# Phiips_212_r2.net
KiCad netlist of a schematic drawn in EAGLE
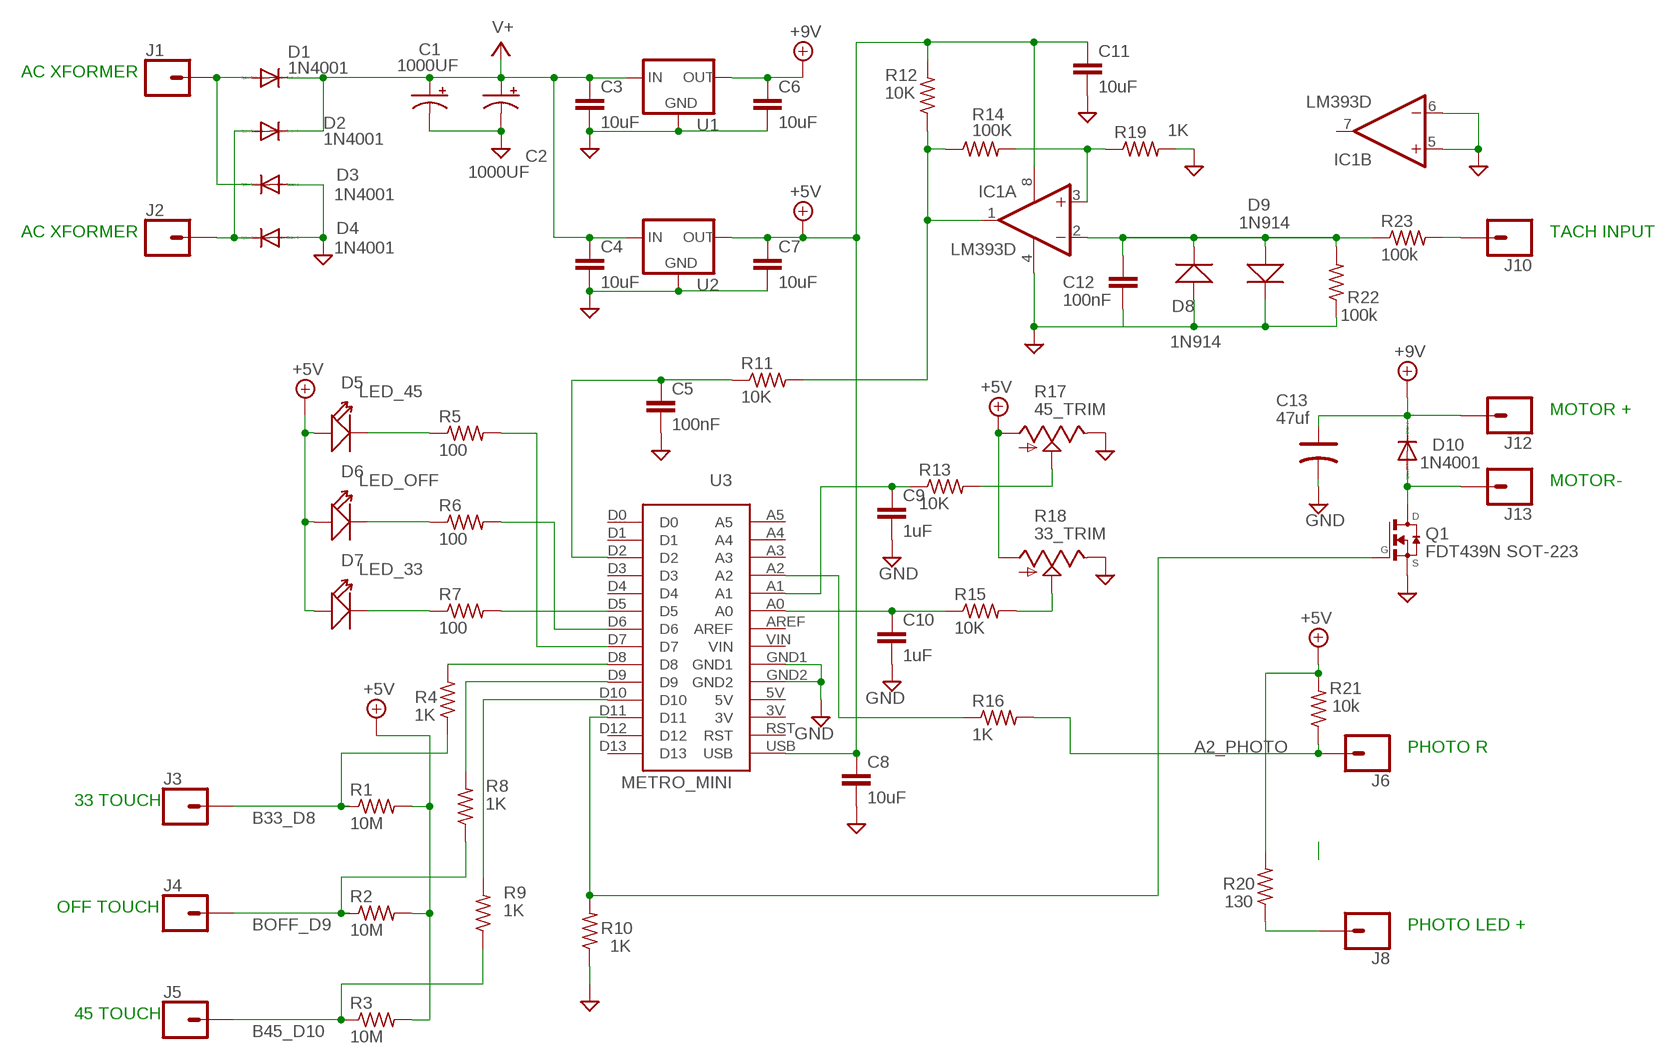
[diagram p0: schematic, sheet 1]

(export (version "E")
  (design (tool "Eeschema 10.0.6"))
  (components
    (comp (ref "C1")
      (value "1000UF")
      (footprint "eagle-import:CAPPAD1700W60L1040D500P")
      (libsource (lib "eagle-import") (part "1000UF"))
    )
    (comp (ref "C2")
      (value "1000UF")
      (footprint "eagle-import:CAPPAD1700W60L1040D500P")
      (libsource (lib "eagle-import") (part "1000UF"))
    )
    (comp (ref "C3")
      (value "10uF")
      (footprint "eagle-import:1206")
      (libsource (lib "eagle-import") (part "10UF-1206-6.3V-20%"))
    )
    (comp (ref "C4")
      (value "10uF")
      (footprint "eagle-import:1206")
      (libsource (lib "eagle-import") (part "10UF-1206-6.3V-20%"))
    )
    (comp (ref "C5")
      (value "100nF")
      (footprint "eagle-import:0805")
      (libsource (lib "eagle-import") (part "10UF-0805-10V-10%"))
    )
    (comp (ref "C6")
      (value "10uF")
      (footprint "eagle-import:1206")
      (libsource (lib "eagle-import") (part "10UF-1206-6.3V-20%"))
    )
    (comp (ref "C7")
      (value "10uF")
      (footprint "eagle-import:1206")
      (libsource (lib "eagle-import") (part "10UF-1206-6.3V-20%"))
    )
    (comp (ref "C8")
      (value "10uF")
      (footprint "eagle-import:1206")
      (libsource (lib "eagle-import") (part "10UF-1206-6.3V-20%"))
    )
    (comp (ref "C9")
      (value "1uF")
      (footprint "eagle-import:1206")
      (libsource (lib "eagle-import") (part "10UF-1206-6.3V-20%"))
    )
    (comp (ref "C10")
      (value "1uF")
      (footprint "eagle-import:1206")
      (libsource (lib "eagle-import") (part "10UF-1206-6.3V-20%"))
    )
    (comp (ref "C11")
      (value "10uF")
      (footprint "eagle-import:1206")
      (libsource (lib "eagle-import") (part "10UF-1206-6.3V-20%"))
    )
    (comp (ref "C12")
      (value "100nF")
      (footprint "eagle-import:0805")
      (libsource (lib "eagle-import") (part "10UF-0805-10V-10%"))
    )
    (comp (ref "C13")
      (value "47uf")
      (footprint "eagle-import:AVX-D")
      (fields (field (name "MPN") "TAJD477*006#NJ"))
      (libsource (lib "eagle-import") (part "TANTALUM-SMD-470UF-6.3V(AVX-D)"))
    )
    (comp (ref "D1")
      (value "1N4001")
      (footprint "eagle-import:DO41-10")
      (libsource (lib "eagle-import") (part "1N4004"))
    )
    (comp (ref "D2")
      (value "1N4001")
      (footprint "eagle-import:DO41-10")
      (libsource (lib "eagle-import") (part "1N4004"))
    )
    (comp (ref "D3")
      (value "1N4001")
      (footprint "eagle-import:DO41-10")
      (libsource (lib "eagle-import") (part "1N4004"))
    )
    (comp (ref "D4")
      (value "1N4001")
      (footprint "eagle-import:DO41-10")
      (libsource (lib "eagle-import") (part "1N4004"))
    )
    (comp (ref "D5")
      (value "LED_45")
      (footprint "eagle-import:LED2-2.54-D5.0MM")
      (fields (field (name "MPN") "504WC"))
      (libsource (lib "eagle-import") (part "DIP-LED-TRANSPARENT-WHITE(2P-D5MM)"))
    )
    (comp (ref "D6")
      (value "LED_OFF")
      (footprint "eagle-import:LED2-2.54-D5.0MM")
      (fields (field (name "MPN") "504WC"))
      (libsource (lib "eagle-import") (part "DIP-LED-TRANSPARENT-WHITE(2P-D5MM)"))
    )
    (comp (ref "D7")
      (value "LED_33")
      (footprint "eagle-import:LED2-2.54-D5.0MM")
      (fields (field (name "MPN") "504WC"))
      (libsource (lib "eagle-import") (part "DIP-LED-TRANSPARENT-WHITE(2P-D5MM)"))
    )
    (comp (ref "D8")
      (value "1N914")
      (footprint "eagle-import:DO-41")
      (fields (field (name "MPN") "1N4004"))
      (libsource (lib "eagle-import") (part "DIP-DIODE-400V-1A(DO-41)"))
    )
    (comp (ref "D9")
      (value "1N914")
      (footprint "eagle-import:DO-41")
      (fields (field (name "MPN") "1N4004"))
      (libsource (lib "eagle-import") (part "DIP-DIODE-400V-1A(DO-41)"))
    )
    (comp (ref "D10")
      (value "1N4001")
      (footprint "eagle-import:DO41-10")
      (libsource (lib "eagle-import") (part "1N4004"))
    )
    (comp (ref "IC1")
      (value "LM393D")
      (footprint "eagle-import:SO08")
      (libsource (lib "eagle-import") (part "LM393D"))
    )
    (comp (ref "J1")
      (value "CONN_01OFFSET")
      (footprint "eagle-import:1X01_OFFSET")
      (libsource (lib "eagle-import") (part "CONN_01OFFSET"))
    )
    (comp (ref "J2")
      (value "CONN_01OFFSET")
      (footprint "eagle-import:1X01_OFFSET")
      (libsource (lib "eagle-import") (part "CONN_01OFFSET"))
    )
    (comp (ref "J3")
      (value "CONN_01OFFSET")
      (footprint "eagle-import:1X01_OFFSET")
      (libsource (lib "eagle-import") (part "CONN_01OFFSET"))
    )
    (comp (ref "J4")
      (value "CONN_01OFFSET")
      (footprint "eagle-import:1X01_OFFSET")
      (libsource (lib "eagle-import") (part "CONN_01OFFSET"))
    )
    (comp (ref "J5")
      (value "CONN_01OFFSET")
      (footprint "eagle-import:1X01_OFFSET")
      (libsource (lib "eagle-import") (part "CONN_01OFFSET"))
    )
    (comp (ref "J6")
      (value "CONN_01OFFSET")
      (footprint "eagle-import:1X01_OFFSET")
      (libsource (lib "eagle-import") (part "CONN_01OFFSET"))
    )
    (comp (ref "J8")
      (value "CONN_01OFFSET")
      (footprint "eagle-import:1X01_OFFSET")
      (libsource (lib "eagle-import") (part "CONN_01OFFSET"))
    )
    (comp (ref "J10")
      (value "CONN_01OFFSET")
      (footprint "eagle-import:1X01_OFFSET")
      (libsource (lib "eagle-import") (part "CONN_01OFFSET"))
    )
    (comp (ref "J12")
      (value "CONN_01OFFSET")
      (footprint "eagle-import:1X01_OFFSET")
      (libsource (lib "eagle-import") (part "CONN_01OFFSET"))
    )
    (comp (ref "J13")
      (value "CONN_01OFFSET")
      (footprint "eagle-import:1X01_OFFSET")
      (libsource (lib "eagle-import") (part "CONN_01OFFSET"))
    )
    (comp (ref "Q1")
      (value "FDT439N SOT-223")
      (footprint "eagle-import:SOT-223")
      (libsource (lib "eagle-import") (part "FDT439NSOT-223"))
    )
    (comp (ref "R1")
      (value "10M")
      (footprint "eagle-import:M1206")
      (libsource (lib "eagle-import") (part "R-US_M1206"))
    )
    (comp (ref "R2")
      (value "10M")
      (footprint "eagle-import:M1206")
      (libsource (lib "eagle-import") (part "R-US_M1206"))
    )
    (comp (ref "R3")
      (value "10M")
      (footprint "eagle-import:M1206")
      (libsource (lib "eagle-import") (part "R-US_M1206"))
    )
    (comp (ref "R4")
      (value "1K")
      (footprint "eagle-import:M1206")
      (libsource (lib "eagle-import") (part "R-US_M1206"))
    )
    (comp (ref "R5")
      (value "100")
      (footprint "eagle-import:M1206")
      (libsource (lib "eagle-import") (part "R-US_M1206"))
    )
    (comp (ref "R6")
      (value "100")
      (footprint "eagle-import:M1206")
      (libsource (lib "eagle-import") (part "R-US_M1206"))
    )
    (comp (ref "R7")
      (value "100")
      (footprint "eagle-import:M1206")
      (libsource (lib "eagle-import") (part "R-US_M1206"))
    )
    (comp (ref "R8")
      (value "1K")
      (footprint "eagle-import:M1206")
      (libsource (lib "eagle-import") (part "R-US_M1206"))
    )
    (comp (ref "R9")
      (value "1K")
      (footprint "eagle-import:M1206")
      (libsource (lib "eagle-import") (part "R-US_M1206"))
    )
    (comp (ref "R10")
      (value "1K")
      (footprint "eagle-import:M1206")
      (libsource (lib "eagle-import") (part "R-US_M1206"))
    )
    (comp (ref "R11")
      (value "10K")
      (footprint "eagle-import:M1206")
      (libsource (lib "eagle-import") (part "R-US_M1206"))
    )
    (comp (ref "R12")
      (value "10K")
      (footprint "eagle-import:M1206")
      (libsource (lib "eagle-import") (part "R-US_M1206"))
    )
    (comp (ref "R13")
      (value "10K")
      (footprint "eagle-import:M1206")
      (libsource (lib "eagle-import") (part "R-US_M1206"))
    )
    (comp (ref "R14")
      (value "100K")
      (footprint "eagle-import:M1206")
      (libsource (lib "eagle-import") (part "R-US_M1206"))
    )
    (comp (ref "R15")
      (value "10K")
      (footprint "eagle-import:M1206")
      (libsource (lib "eagle-import") (part "R-US_M1206"))
    )
    (comp (ref "R16")
      (value "1K")
      (footprint "eagle-import:M1206")
      (libsource (lib "eagle-import") (part "R-US_M1206"))
    )
    (comp (ref "R17")
      (value "45_TRIM")
      (footprint "eagle-import:PH212_POT")
      (libsource (lib "eagle-import") (part "POTS212_POT"))
    )
    (comp (ref "R18")
      (value "33_TRIM")
      (footprint "eagle-import:PH212_POT")
      (libsource (lib "eagle-import") (part "POTS212_POT"))
    )
    (comp (ref "R19")
      (value "1K")
      (footprint "eagle-import:M1206")
      (libsource (lib "eagle-import") (part "R-US_M1206"))
    )
    (comp (ref "R20")
      (value "130")
      (footprint "eagle-import:M1206")
      (libsource (lib "eagle-import") (part "R-US_M1206"))
    )
    (comp (ref "R21")
      (value "10k")
      (footprint "eagle-import:M1206")
      (libsource (lib "eagle-import") (part "R-US_M1206"))
    )
    (comp (ref "R22")
      (value "100k")
      (footprint "eagle-import:M1206")
      (libsource (lib "eagle-import") (part "R-US_M1206"))
    )
    (comp (ref "R23")
      (value "100k")
      (footprint "eagle-import:M1206")
      (libsource (lib "eagle-import") (part "R-US_M1206"))
    )
    (comp (ref "U1")
      (value "V_REG_78XXSIDE")
      (footprint "eagle-import:78XXL")
      (libsource (lib "eagle-import") (part "V_REG_78XXSIDE"))
    )
    (comp (ref "U2")
      (value "V_REG_78XXSIDE")
      (footprint "eagle-import:78XXL")
      (libsource (lib "eagle-import") (part "V_REG_78XXSIDE"))
    )
    (comp (ref "U3")
      (value "METRO_MINI")
      (footprint "eagle-import:METRO_MINI")
      (libsource (lib "eagle-import") (part "METRO_MINI"))
    )
  )
  (nets
    (net (code "1") (name "+5V") (class "Default")
      (node (ref "C11") (pin "1") (pinfunction "1_1") (pintype "passive"))
      (node (ref "C7") (pin "1") (pinfunction "1_1") (pintype "passive"))
      (node (ref "C8") (pin "1") (pinfunction "1_1") (pintype "passive"))
      (node (ref "D5") (pin "+") (pinfunction "+_+") (pintype "passive"))
      (node (ref "D6") (pin "+") (pinfunction "+_+") (pintype "passive"))
      (node (ref "D7") (pin "+") (pinfunction "+_+") (pintype "passive"))
      (node (ref "IC1") (pin "8") (pinfunction "V+_8") (pintype "power_in"))
      (node (ref "R1") (pin "2") (pinfunction "2_2") (pintype "passive"))
      (node (ref "R12") (pin "2") (pinfunction "2_2") (pintype "passive"))
      (node (ref "R17") (pin "1") (pinfunction "A_1") (pintype "passive"))
      (node (ref "R18") (pin "1") (pinfunction "A_1") (pintype "passive"))
      (node (ref "R2") (pin "2") (pinfunction "2_2") (pintype "passive"))
      (node (ref "R20") (pin "2") (pinfunction "2_2") (pintype "passive"))
      (node (ref "R21") (pin "2") (pinfunction "2_2") (pintype "passive"))
      (node (ref "R3") (pin "2") (pinfunction "2_2") (pintype "passive"))
      (node (ref "U2") (pin "OUT") (pinfunction "OUT_OUT") (pintype "passive"))
      (node (ref "U3") (pin "USB") (pinfunction "USB_USB") (pintype "power_in"))
    )
    (net (code "2") (name "+9V") (class "Default")
      (node (ref "C13") (pin "+") (pinfunction "+_+") (pintype "passive"))
      (node (ref "C6") (pin "1") (pinfunction "1_1") (pintype "passive"))
      (node (ref "D10") (pin "C") (pinfunction "C_C") (pintype "passive"))
      (node (ref "J12") (pin "1") (pinfunction "1_1") (pintype "passive"))
      (node (ref "U1") (pin "OUT") (pinfunction "OUT_OUT") (pintype "passive"))
    )
    (net (code "3") (name "/A2_PHOTO") (class "Default")
      (node (ref "J6") (pin "1") (pinfunction "1_1") (pintype "passive"))
      (node (ref "R16") (pin "2") (pinfunction "2_2") (pintype "passive"))
      (node (ref "R21") (pin "1") (pinfunction "1_1") (pintype "passive"))
    )
    (net (code "4") (name "/B33_D8") (class "Default")
      (node (ref "J3") (pin "1") (pinfunction "1_1") (pintype "passive"))
      (node (ref "R1") (pin "1") (pinfunction "1_1") (pintype "passive"))
      (node (ref "R4") (pin "1") (pinfunction "1_1") (pintype "passive"))
    )
    (net (code "5") (name "/B45_D10") (class "Default")
      (node (ref "J5") (pin "1") (pinfunction "1_1") (pintype "passive"))
      (node (ref "R3") (pin "1") (pinfunction "1_1") (pintype "passive"))
      (node (ref "R9") (pin "1") (pinfunction "1_1") (pintype "passive"))
    )
    (net (code "6") (name "/BOFF_D9") (class "Default")
      (node (ref "J4") (pin "1") (pinfunction "1_1") (pintype "passive"))
      (node (ref "R2") (pin "1") (pinfunction "1_1") (pintype "passive"))
      (node (ref "R8") (pin "1") (pinfunction "1_1") (pintype "passive"))
    )
    (net (code "7") (name "GND") (class "Default")
      (node (ref "C1") (pin "2") (pinfunction "-_2") (pintype "passive"))
      (node (ref "C10") (pin "2") (pinfunction "2_2") (pintype "passive"))
      (node (ref "C11") (pin "2") (pinfunction "2_2") (pintype "passive"))
      (node (ref "C12") (pin "2") (pinfunction "2_2") (pintype "passive"))
      (node (ref "C13") (pin "-") (pinfunction "-_-") (pintype "passive"))
      (node (ref "C2") (pin "2") (pinfunction "-_2") (pintype "passive"))
      (node (ref "C3") (pin "2") (pinfunction "2_2") (pintype "passive"))
      (node (ref "C4") (pin "2") (pinfunction "2_2") (pintype "passive"))
      (node (ref "C5") (pin "2") (pinfunction "2_2") (pintype "passive"))
      (node (ref "C6") (pin "2") (pinfunction "2_2") (pintype "passive"))
      (node (ref "C7") (pin "2") (pinfunction "2_2") (pintype "passive"))
      (node (ref "C8") (pin "2") (pinfunction "2_2") (pintype "passive"))
      (node (ref "C9") (pin "2") (pinfunction "2_2") (pintype "passive"))
      (node (ref "D3") (pin "A") (pinfunction "A_A") (pintype "passive"))
      (node (ref "D4") (pin "A") (pinfunction "A_A") (pintype "passive"))
      (node (ref "D8") (pin "1") (pinfunction "+_1") (pintype "passive"))
      (node (ref "D9") (pin "2") (pinfunction "-_2") (pintype "passive"))
      (node (ref "IC1") (pin "4") (pinfunction "V-_4") (pintype "power_in"))
      (node (ref "IC1") (pin "5") (pinfunction "+IN_5") (pintype "input"))
      (node (ref "IC1") (pin "6") (pinfunction "-IN_6") (pintype "input"))
      (node (ref "Q1") (pin "3") (pinfunction "S_3") (pintype "passive"))
      (node (ref "R10") (pin "1") (pinfunction "1_1") (pintype "passive"))
      (node (ref "R17") (pin "3") (pinfunction "E_3") (pintype "passive"))
      (node (ref "R18") (pin "3") (pinfunction "E_3") (pintype "passive"))
      (node (ref "R19") (pin "2") (pinfunction "2_2") (pintype "passive"))
      (node (ref "R22") (pin "1") (pinfunction "1_1") (pintype "passive"))
      (node (ref "U1") (pin "GND") (pinfunction "GND_GND") (pintype "input"))
      (node (ref "U2") (pin "GND") (pinfunction "GND_GND") (pintype "input"))
      (node (ref "U3") (pin "GND1") (pinfunction "GND1_GND1") (pintype "power_in"))
      (node (ref "U3") (pin "GND2") (pinfunction "GND2_GND2") (pintype "power_in"))
    )
    (net (code "8") (name "Net-(C5-Pad1)") (class "Default")
      (node (ref "C5") (pin "1") (pinfunction "1_1") (pintype "passive"))
      (node (ref "R11") (pin "1") (pinfunction "1_1") (pintype "passive"))
      (node (ref "U3") (pin "D2") (pinfunction "D2_D2") (pintype "bidirectional"))
    )
    (net (code "9") (name "Net-(C9-Pad1)") (class "Default")
      (node (ref "C9") (pin "1") (pinfunction "1_1") (pintype "passive"))
      (node (ref "R13") (pin "1") (pinfunction "1_1") (pintype "passive"))
      (node (ref "U3") (pin "A1") (pinfunction "A1_A1") (pintype "bidirectional"))
    )
    (net (code "10") (name "Net-(C10-Pad1)") (class "Default")
      (node (ref "C10") (pin "1") (pinfunction "1_1") (pintype "passive"))
      (node (ref "R15") (pin "1") (pinfunction "1_1") (pintype "passive"))
      (node (ref "U3") (pin "A0") (pinfunction "A0_A0") (pintype "bidirectional"))
    )
    (net (code "11") (name "Net-(D1-PadA)") (class "Default")
      (node (ref "D1") (pin "A") (pinfunction "A_A") (pintype "passive"))
      (node (ref "D3") (pin "C") (pinfunction "C_C") (pintype "passive"))
      (node (ref "J1") (pin "1") (pinfunction "1_1") (pintype "passive"))
    )
    (net (code "12") (name "Net-(D2-PadA)") (class "Default")
      (node (ref "D2") (pin "A") (pinfunction "A_A") (pintype "passive"))
      (node (ref "D4") (pin "C") (pinfunction "C_C") (pintype "passive"))
      (node (ref "J2") (pin "1") (pinfunction "1_1") (pintype "passive"))
    )
    (net (code "13") (name "Net-(D5-Pad-)") (class "Default")
      (node (ref "D5") (pin "-") (pinfunction "-_-") (pintype "passive"))
      (node (ref "R5") (pin "1") (pinfunction "1_1") (pintype "passive"))
    )
    (net (code "14") (name "Net-(D6-Pad-)") (class "Default")
      (node (ref "D6") (pin "-") (pinfunction "-_-") (pintype "passive"))
      (node (ref "R6") (pin "1") (pinfunction "1_1") (pintype "passive"))
    )
    (net (code "15") (name "Net-(D7-Pad-)") (class "Default")
      (node (ref "D7") (pin "-") (pinfunction "-_-") (pintype "passive"))
      (node (ref "R7") (pin "1") (pinfunction "1_1") (pintype "passive"))
    )
    (net (code "16") (name "Net-(D8--)") (class "Default")
      (node (ref "C12") (pin "1") (pinfunction "1_1") (pintype "passive"))
      (node (ref "D8") (pin "2") (pinfunction "-_2") (pintype "passive"))
      (node (ref "D9") (pin "1") (pinfunction "+_1") (pintype "passive"))
      (node (ref "IC1") (pin "2") (pinfunction "-IN_2") (pintype "input"))
      (node (ref "R22") (pin "2") (pinfunction "2_2") (pintype "passive"))
      (node (ref "R23") (pin "1") (pinfunction "1_1") (pintype "passive"))
    )
    (net (code "17") (name "Net-(D10-PadA)") (class "Default")
      (node (ref "D10") (pin "A") (pinfunction "A_A") (pintype "passive"))
      (node (ref "J13") (pin "1") (pinfunction "1_1") (pintype "passive"))
      (node (ref "Q1") (pin "2") (pinfunction "D_2") (pintype "passive"))
      (node (ref "Q1") (pin "4") (pinfunction "D_4") (pintype "passive"))
    )
    (net (code "18") (name "Net-(IC1A-+IN)") (class "Default")
      (node (ref "IC1") (pin "3") (pinfunction "+IN_3") (pintype "input"))
      (node (ref "R14") (pin "2") (pinfunction "2_2") (pintype "passive"))
      (node (ref "R19") (pin "1") (pinfunction "1_1") (pintype "passive"))
    )
    (net (code "19") (name "Net-(IC1A-OUT)") (class "Default")
      (node (ref "IC1") (pin "1") (pinfunction "OUT_1") (pintype "output"))
      (node (ref "R11") (pin "2") (pinfunction "2_2") (pintype "passive"))
      (node (ref "R12") (pin "1") (pinfunction "1_1") (pintype "passive"))
      (node (ref "R14") (pin "1") (pinfunction "1_1") (pintype "passive"))
    )
    (net (code "20") (name "Net-(J8-Pad1)") (class "Default")
      (node (ref "J8") (pin "1") (pinfunction "1_1") (pintype "passive"))
      (node (ref "R20") (pin "1") (pinfunction "1_1") (pintype "passive"))
    )
    (net (code "21") (name "Net-(J10-Pad1)") (class "Default")
      (node (ref "J10") (pin "1") (pinfunction "1_1") (pintype "passive"))
      (node (ref "R23") (pin "2") (pinfunction "2_2") (pintype "passive"))
    )
    (net (code "22") (name "Net-(Q1-G)") (class "Default")
      (node (ref "Q1") (pin "1") (pinfunction "G_1") (pintype "passive"))
      (node (ref "R10") (pin "2") (pinfunction "2_2") (pintype "passive"))
      (node (ref "U3") (pin "D11") (pinfunction "D11_D11") (pintype "bidirectional"))
    )
    (net (code "23") (name "Net-(R4-Pad2)") (class "Default")
      (node (ref "R4") (pin "2") (pinfunction "2_2") (pintype "passive"))
      (node (ref "U3") (pin "D8") (pinfunction "D8_D8") (pintype "bidirectional"))
    )
    (net (code "24") (name "Net-(R5-Pad2)") (class "Default")
      (node (ref "R5") (pin "2") (pinfunction "2_2") (pintype "passive"))
      (node (ref "U3") (pin "D7") (pinfunction "D7_D7") (pintype "bidirectional"))
    )
    (net (code "25") (name "Net-(R6-Pad2)") (class "Default")
      (node (ref "R6") (pin "2") (pinfunction "2_2") (pintype "passive"))
      (node (ref "U3") (pin "D6") (pinfunction "D6_D6") (pintype "bidirectional"))
    )
    (net (code "26") (name "Net-(R7-Pad2)") (class "Default")
      (node (ref "R7") (pin "2") (pinfunction "2_2") (pintype "passive"))
      (node (ref "U3") (pin "D5") (pinfunction "D5_D5") (pintype "bidirectional"))
    )
    (net (code "27") (name "Net-(R8-Pad2)") (class "Default")
      (node (ref "R8") (pin "2") (pinfunction "2_2") (pintype "passive"))
      (node (ref "U3") (pin "D9") (pinfunction "D9_D9") (pintype "bidirectional"))
    )
    (net (code "28") (name "Net-(R9-Pad2)") (class "Default")
      (node (ref "R9") (pin "2") (pinfunction "2_2") (pintype "passive"))
      (node (ref "U3") (pin "D10") (pinfunction "D10_D10") (pintype "bidirectional"))
    )
    (net (code "29") (name "Net-(R16-Pad1)") (class "Default")
      (node (ref "R16") (pin "1") (pinfunction "1_1") (pintype "passive"))
      (node (ref "U3") (pin "A2") (pinfunction "A2_A2") (pintype "bidirectional"))
    )
    (net (code "30") (name "Net-(R17-S)") (class "Default")
      (node (ref "R13") (pin "2") (pinfunction "2_2") (pintype "passive"))
      (node (ref "R17") (pin "2") (pinfunction "S_2") (pintype "passive"))
    )
    (net (code "31") (name "Net-(R18-S)") (class "Default")
      (node (ref "R15") (pin "2") (pinfunction "2_2") (pintype "passive"))
      (node (ref "R18") (pin "2") (pinfunction "S_2") (pintype "passive"))
    )
    (net (code "32") (name "V+") (class "Default")
      (node (ref "C1") (pin "1") (pinfunction "+_1") (pintype "passive"))
      (node (ref "C2") (pin "1") (pinfunction "+_1") (pintype "passive"))
      (node (ref "C3") (pin "1") (pinfunction "1_1") (pintype "passive"))
      (node (ref "C4") (pin "1") (pinfunction "1_1") (pintype "passive"))
      (node (ref "D1") (pin "C") (pinfunction "C_C") (pintype "passive"))
      (node (ref "D2") (pin "C") (pinfunction "C_C") (pintype "passive"))
      (node (ref "U1") (pin "IN") (pinfunction "IN_IN") (pintype "input"))
      (node (ref "U2") (pin "IN") (pinfunction "IN_IN") (pintype "input"))
    )
    (net (code "33") (name "unconnected-(IC1B-OUT-Pad7)") (class "Default")
      (node (ref "IC1") (pin "7") (pinfunction "OUT_7") (pintype "output"))
    )
    (net (code "34") (name "unconnected-(U3-Pad3V)") (class "Default")
      (node (ref "U3") (pin "3V") (pinfunction "3V_3V") (pintype "bidirectional"))
    )
    (net (code "35") (name "unconnected-(U3-Pad5V)") (class "Default")
      (node (ref "U3") (pin "5V") (pinfunction "5V_5V") (pintype "bidirectional"))
    )
    (net (code "36") (name "unconnected-(U3-PadA3)") (class "Default")
      (node (ref "U3") (pin "A3") (pinfunction "A3_A3") (pintype "bidirectional"))
    )
    (net (code "37") (name "unconnected-(U3-PadA4)") (class "Default")
      (node (ref "U3") (pin "A4") (pinfunction "A4_A4") (pintype "bidirectional"))
    )
    (net (code "38") (name "unconnected-(U3-PadA5)") (class "Default")
      (node (ref "U3") (pin "A5") (pinfunction "A5_A5") (pintype "bidirectional"))
    )
    (net (code "39") (name "unconnected-(U3-PadAREF)") (class "Default")
      (node (ref "U3") (pin "AREF") (pinfunction "AREF_AREF") (pintype "bidirectional"))
    )
    (net (code "40") (name "unconnected-(U3-PadD0)") (class "Default")
      (node (ref "U3") (pin "D0") (pinfunction "D0_D0") (pintype "bidirectional"))
    )
    (net (code "41") (name "unconnected-(U3-PadD1)") (class "Default")
      (node (ref "U3") (pin "D1") (pinfunction "D1_D1") (pintype "bidirectional"))
    )
    (net (code "42") (name "unconnected-(U3-PadD3)") (class "Default")
      (node (ref "U3") (pin "D3") (pinfunction "D3_D3") (pintype "bidirectional"))
    )
    (net (code "43") (name "unconnected-(U3-PadD4)") (class "Default")
      (node (ref "U3") (pin "D4") (pinfunction "D4_D4") (pintype "bidirectional"))
    )
    (net (code "44") (name "unconnected-(U3-PadD12)") (class "Default")
      (node (ref "U3") (pin "D12") (pinfunction "D12_D12") (pintype "bidirectional"))
    )
    (net (code "45") (name "unconnected-(U3-PadD13)") (class "Default")
      (node (ref "U3") (pin "D13") (pinfunction "D13_D13") (pintype "bidirectional"))
    )
    (net (code "46") (name "unconnected-(U3-PadRST)") (class "Default")
      (node (ref "U3") (pin "RST") (pinfunction "RST_RST") (pintype "bidirectional"))
    )
    (net (code "47") (name "unconnected-(U3-PadVIN)") (class "Default")
      (node (ref "U3") (pin "VIN") (pinfunction "VIN_VIN") (pintype "bidirectional"))
    )
  )
)
